# 13-Counter74LS90.net
KiCad netlist of a schematic drawn in Altium Designer
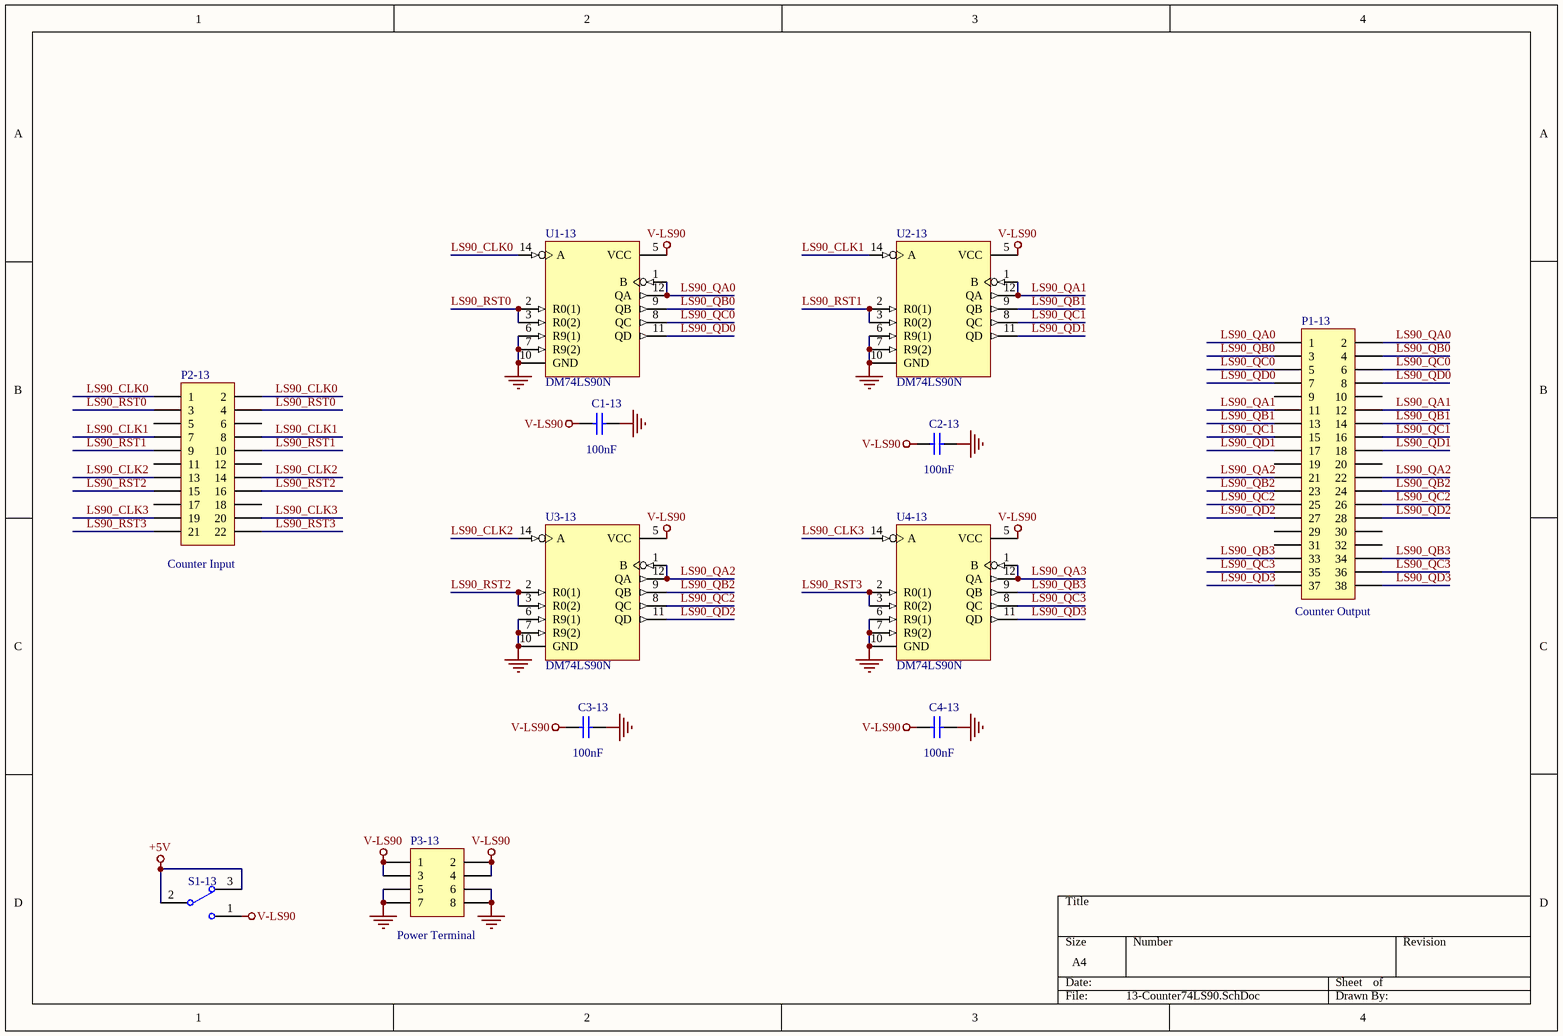
[diagram p0: 13-Counter74LS90.SchDoc]

(export (version "E")
  (design (tool "Eeschema 10.0.6"))
  (components
    (comp (ref "C1-13")
      (value "100nF")
      (footprint "c-0805")
      (description "Capacitor")
      (fields (field (name "Comment") "104") (field (name "PUBLISHER") "Altium Limited"))
      (libsource (lib "Miscellaneous Devices") (part "Cap"))
    )
    (comp (ref "C2-13")
      (value "100nF")
      (footprint "c-0805")
      (description "Capacitor")
      (fields (field (name "Comment") "104") (field (name "PUBLISHER") "Altium Limited"))
      (libsource (lib "Miscellaneous Devices") (part "Cap"))
    )
    (comp (ref "C3-13")
      (value "100nF")
      (footprint "c-0805")
      (description "Capacitor")
      (fields (field (name "Comment") "104") (field (name "PUBLISHER") "Altium Limited"))
      (libsource (lib "Miscellaneous Devices") (part "Cap"))
    )
    (comp (ref "C4-13")
      (value "100nF")
      (footprint "c-0805")
      (description "Capacitor")
      (fields (field (name "Comment") "104") (field (name "PUBLISHER") "Altium Limited"))
      (libsource (lib "Miscellaneous Devices") (part "Cap"))
    )
    (comp (ref "P1-13")
      (value "Counter Output")
      (footprint "JP2.54-F-2x19A")
      (description "Header, 19-Pin, Dual row")
      (fields (field (name "Comment") "Header 19X2"))
      (libsource (lib "Miscellaneous Connectors") (part "Header 19X2"))
    )
    (comp (ref "P2-13")
      (value "Counter Input")
      (footprint "JP2.54-F-2x11A")
      (description "Header, 11-Pin, Dual row")
      (fields (field (name "Comment") "Header 11X2"))
      (libsource (lib "Miscellaneous Connectors") (part "Header 11X2"))
    )
    (comp (ref "P3-13")
      (value "Header 4X2")
      (footprint "JP2.54-F-2x04A")
      (description "Header, 4-Pin, Dual row")
      (fields (field (name "PUBLISHER") "Power Terminal"))
      (libsource (lib "Miscellaneous Connectors") (part "Header 4X2"))
    )
    (comp (ref "S1-13")
      (value "SW-SPDT")
      (footprint "SW-SLIDE-2P-2W")
      (description "SPDT Subminiature Toggle Switch, Right Angle Mounting, Vertical Actuation")
      (fields (field (name "PUBLISHER") "Altium Limited"))
      (libsource (lib "Miscellaneous Devices") (part "SW-SPDT"))
    )
    (comp (ref "U1-13")
      (value "DM74LS90N")
      (footprint "SK-DIP14-300")
      (description "Decade and Binary Counter")
      (fields (field (name "PUBLISHER") "Altium Limited"))
      (libsource (lib "FSC Logic Counter") (part "DM74LS90N"))
    )
    (comp (ref "U2-13")
      (value "DM74LS90N")
      (footprint "SK-DIP14-300")
      (description "Decade and Binary Counter")
      (fields (field (name "PUBLISHER") "Altium Limited"))
      (libsource (lib "FSC Logic Counter") (part "DM74LS90N"))
    )
    (comp (ref "U3-13")
      (value "DM74LS90N")
      (footprint "SK-DIP14-300")
      (description "Decade and Binary Counter")
      (fields (field (name "PUBLISHER") "Altium Limited"))
      (libsource (lib "FSC Logic Counter") (part "DM74LS90N"))
    )
    (comp (ref "U4-13")
      (value "DM74LS90N")
      (footprint "SK-DIP14-300")
      (description "Decade and Binary Counter")
      (fields (field (name "PUBLISHER") "Altium Limited"))
      (libsource (lib "FSC Logic Counter") (part "DM74LS90N"))
    )
  )
  (nets
    (net (code "1") (name "+5V") (class "Default")
      (node (ref "S1-13") (pin "2") (pinfunction "2_2") (pintype "passive"))
      (node (ref "S1-13") (pin "3") (pinfunction "3_3") (pintype "passive"))
    )
    (net (code "2") (name "/LS90_CLK0") (class "Default")
      (node (ref "P2-13") (pin "1") (pinfunction "1_1") (pintype "passive"))
      (node (ref "P2-13") (pin "2") (pinfunction "2_2") (pintype "passive"))
      (node (ref "U1-13") (pin "14") (pinfunction "A_14") (pintype "input"))
    )
    (net (code "3") (name "/LS90_CLK1") (class "Default")
      (node (ref "P2-13") (pin "7") (pinfunction "7_7") (pintype "passive"))
      (node (ref "P2-13") (pin "8") (pinfunction "8_8") (pintype "passive"))
      (node (ref "U2-13") (pin "14") (pinfunction "A_14") (pintype "input"))
    )
    (net (code "4") (name "/LS90_CLK2") (class "Default")
      (node (ref "P2-13") (pin "13") (pinfunction "13_13") (pintype "passive"))
      (node (ref "P2-13") (pin "14") (pinfunction "14_14") (pintype "passive"))
      (node (ref "U3-13") (pin "14") (pinfunction "A_14") (pintype "input"))
    )
    (net (code "5") (name "/LS90_CLK3") (class "Default")
      (node (ref "P2-13") (pin "19") (pinfunction "19_19") (pintype "passive"))
      (node (ref "P2-13") (pin "20") (pinfunction "20_20") (pintype "passive"))
      (node (ref "U4-13") (pin "14") (pinfunction "A_14") (pintype "input"))
    )
    (net (code "6") (name "/LS90_QA0") (class "Default")
      (node (ref "P1-13") (pin "1") (pinfunction "1_1") (pintype "passive"))
      (node (ref "P1-13") (pin "2") (pinfunction "2_2") (pintype "passive"))
      (node (ref "U1-13") (pin "1") (pinfunction "B_1") (pintype "input"))
      (node (ref "U1-13") (pin "12") (pinfunction "QA_12") (pintype "output"))
    )
    (net (code "7") (name "/LS90_QA1") (class "Default")
      (node (ref "P1-13") (pin "11") (pinfunction "11_11") (pintype "passive"))
      (node (ref "P1-13") (pin "12") (pinfunction "12_12") (pintype "passive"))
      (node (ref "U2-13") (pin "1") (pinfunction "B_1") (pintype "input"))
      (node (ref "U2-13") (pin "12") (pinfunction "QA_12") (pintype "output"))
    )
    (net (code "8") (name "/LS90_QA2") (class "Default")
      (node (ref "P1-13") (pin "21") (pinfunction "21_21") (pintype "passive"))
      (node (ref "P1-13") (pin "22") (pinfunction "22_22") (pintype "passive"))
      (node (ref "U3-13") (pin "1") (pinfunction "B_1") (pintype "input"))
      (node (ref "U3-13") (pin "12") (pinfunction "QA_12") (pintype "output"))
    )
    (net (code "9") (name "/LS90_QA3") (class "Default")
      (node (ref "U4-13") (pin "1") (pinfunction "B_1") (pintype "input"))
      (node (ref "U4-13") (pin "12") (pinfunction "QA_12") (pintype "output"))
    )
    (net (code "10") (name "/LS90_QB0") (class "Default")
      (node (ref "P1-13") (pin "3") (pinfunction "3_3") (pintype "passive"))
      (node (ref "P1-13") (pin "4") (pinfunction "4_4") (pintype "passive"))
      (node (ref "U1-13") (pin "9") (pinfunction "QB_9") (pintype "output"))
    )
    (net (code "11") (name "/LS90_QB1") (class "Default")
      (node (ref "P1-13") (pin "13") (pinfunction "13_13") (pintype "passive"))
      (node (ref "P1-13") (pin "14") (pinfunction "14_14") (pintype "passive"))
      (node (ref "U2-13") (pin "9") (pinfunction "QB_9") (pintype "output"))
    )
    (net (code "12") (name "/LS90_QB2") (class "Default")
      (node (ref "P1-13") (pin "23") (pinfunction "23_23") (pintype "passive"))
      (node (ref "P1-13") (pin "24") (pinfunction "24_24") (pintype "passive"))
      (node (ref "U3-13") (pin "9") (pinfunction "QB_9") (pintype "output"))
    )
    (net (code "13") (name "/LS90_QB3") (class "Default")
      (node (ref "P1-13") (pin "33") (pinfunction "33_33") (pintype "passive"))
      (node (ref "P1-13") (pin "34") (pinfunction "34_34") (pintype "passive"))
      (node (ref "U4-13") (pin "9") (pinfunction "QB_9") (pintype "output"))
    )
    (net (code "14") (name "/LS90_QC0") (class "Default")
      (node (ref "P1-13") (pin "5") (pinfunction "5_5") (pintype "passive"))
      (node (ref "P1-13") (pin "6") (pinfunction "6_6") (pintype "passive"))
      (node (ref "U1-13") (pin "8") (pinfunction "QC_8") (pintype "output"))
    )
    (net (code "15") (name "/LS90_QC1") (class "Default")
      (node (ref "P1-13") (pin "15") (pinfunction "15_15") (pintype "passive"))
      (node (ref "P1-13") (pin "16") (pinfunction "16_16") (pintype "passive"))
      (node (ref "U2-13") (pin "8") (pinfunction "QC_8") (pintype "output"))
    )
    (net (code "16") (name "/LS90_QC2") (class "Default")
      (node (ref "P1-13") (pin "25") (pinfunction "25_25") (pintype "passive"))
      (node (ref "P1-13") (pin "26") (pinfunction "26_26") (pintype "passive"))
      (node (ref "U3-13") (pin "8") (pinfunction "QC_8") (pintype "output"))
    )
    (net (code "17") (name "/LS90_QC3") (class "Default")
      (node (ref "P1-13") (pin "35") (pinfunction "35_35") (pintype "passive"))
      (node (ref "P1-13") (pin "36") (pinfunction "36_36") (pintype "passive"))
      (node (ref "U4-13") (pin "8") (pinfunction "QC_8") (pintype "output"))
    )
    (net (code "18") (name "/LS90_QD0") (class "Default")
      (node (ref "P1-13") (pin "7") (pinfunction "7_7") (pintype "passive"))
      (node (ref "P1-13") (pin "8") (pinfunction "8_8") (pintype "passive"))
      (node (ref "U1-13") (pin "11") (pinfunction "QD_11") (pintype "output"))
    )
    (net (code "19") (name "/LS90_QD1") (class "Default")
      (node (ref "P1-13") (pin "17") (pinfunction "17_17") (pintype "passive"))
      (node (ref "P1-13") (pin "18") (pinfunction "18_18") (pintype "passive"))
      (node (ref "U2-13") (pin "11") (pinfunction "QD_11") (pintype "output"))
    )
    (net (code "20") (name "/LS90_QD2") (class "Default")
      (node (ref "P1-13") (pin "27") (pinfunction "27_27") (pintype "passive"))
      (node (ref "P1-13") (pin "28") (pinfunction "28_28") (pintype "passive"))
      (node (ref "U3-13") (pin "11") (pinfunction "QD_11") (pintype "output"))
    )
    (net (code "21") (name "/LS90_QD3") (class "Default")
      (node (ref "P1-13") (pin "37") (pinfunction "37_37") (pintype "passive"))
      (node (ref "P1-13") (pin "38") (pinfunction "38_38") (pintype "passive"))
      (node (ref "U4-13") (pin "11") (pinfunction "QD_11") (pintype "output"))
    )
    (net (code "22") (name "/LS90_RST0") (class "Default")
      (node (ref "P2-13") (pin "3") (pinfunction "3_3") (pintype "passive"))
      (node (ref "P2-13") (pin "4") (pinfunction "4_4") (pintype "passive"))
      (node (ref "U1-13") (pin "2") (pinfunction "R0(1)_2") (pintype "input"))
      (node (ref "U1-13") (pin "3") (pinfunction "R0(2)_3") (pintype "input"))
    )
    (net (code "23") (name "/LS90_RST1") (class "Default")
      (node (ref "P2-13") (pin "10") (pinfunction "10_10") (pintype "passive"))
      (node (ref "P2-13") (pin "9") (pinfunction "9_9") (pintype "passive"))
      (node (ref "U2-13") (pin "2") (pinfunction "R0(1)_2") (pintype "input"))
      (node (ref "U2-13") (pin "3") (pinfunction "R0(2)_3") (pintype "input"))
    )
    (net (code "24") (name "/LS90_RST2") (class "Default")
      (node (ref "P2-13") (pin "15") (pinfunction "15_15") (pintype "passive"))
      (node (ref "P2-13") (pin "16") (pinfunction "16_16") (pintype "passive"))
      (node (ref "U3-13") (pin "2") (pinfunction "R0(1)_2") (pintype "input"))
      (node (ref "U3-13") (pin "3") (pinfunction "R0(2)_3") (pintype "input"))
    )
    (net (code "25") (name "/LS90_RST3") (class "Default")
      (node (ref "P2-13") (pin "21") (pinfunction "21_21") (pintype "passive"))
      (node (ref "P2-13") (pin "22") (pinfunction "22_22") (pintype "passive"))
      (node (ref "U4-13") (pin "2") (pinfunction "R0(1)_2") (pintype "input"))
      (node (ref "U4-13") (pin "3") (pinfunction "R0(2)_3") (pintype "input"))
    )
    (net (code "26") (name "GND") (class "Default")
      (node (ref "C1-13") (pin "2") (pinfunction "2_2") (pintype "passive"))
      (node (ref "C2-13") (pin "2") (pinfunction "2_2") (pintype "passive"))
      (node (ref "C3-13") (pin "2") (pinfunction "2_2") (pintype "passive"))
      (node (ref "C4-13") (pin "2") (pinfunction "2_2") (pintype "passive"))
      (node (ref "P3-13") (pin "5") (pinfunction "5_5") (pintype "passive"))
      (node (ref "P3-13") (pin "6") (pinfunction "6_6") (pintype "passive"))
      (node (ref "P3-13") (pin "7") (pinfunction "7_7") (pintype "passive"))
      (node (ref "P3-13") (pin "8") (pinfunction "8_8") (pintype "passive"))
      (node (ref "U1-13") (pin "10") (pinfunction "GND_10") (pintype "power_in"))
      (node (ref "U1-13") (pin "6") (pinfunction "R9(1)_6") (pintype "input"))
      (node (ref "U1-13") (pin "7") (pinfunction "R9(2)_7") (pintype "input"))
      (node (ref "U2-13") (pin "10") (pinfunction "GND_10") (pintype "power_in"))
      (node (ref "U2-13") (pin "6") (pinfunction "R9(1)_6") (pintype "input"))
      (node (ref "U2-13") (pin "7") (pinfunction "R9(2)_7") (pintype "input"))
      (node (ref "U3-13") (pin "10") (pinfunction "GND_10") (pintype "power_in"))
      (node (ref "U3-13") (pin "6") (pinfunction "R9(1)_6") (pintype "input"))
      (node (ref "U3-13") (pin "7") (pinfunction "R9(2)_7") (pintype "input"))
      (node (ref "U4-13") (pin "10") (pinfunction "GND_10") (pintype "power_in"))
      (node (ref "U4-13") (pin "6") (pinfunction "R9(1)_6") (pintype "input"))
      (node (ref "U4-13") (pin "7") (pinfunction "R9(2)_7") (pintype "input"))
    )
    (net (code "27") (name "V-LS90") (class "Default")
      (node (ref "C1-13") (pin "1") (pinfunction "1_1") (pintype "passive"))
      (node (ref "C2-13") (pin "1") (pinfunction "1_1") (pintype "passive"))
      (node (ref "C3-13") (pin "1") (pinfunction "1_1") (pintype "passive"))
      (node (ref "C4-13") (pin "1") (pinfunction "1_1") (pintype "passive"))
      (node (ref "P3-13") (pin "1") (pinfunction "1_1") (pintype "passive"))
      (node (ref "P3-13") (pin "2") (pinfunction "2_2") (pintype "passive"))
      (node (ref "P3-13") (pin "3") (pinfunction "3_3") (pintype "passive"))
      (node (ref "P3-13") (pin "4") (pinfunction "4_4") (pintype "passive"))
      (node (ref "S1-13") (pin "1") (pinfunction "1_1") (pintype "passive"))
      (node (ref "U1-13") (pin "5") (pinfunction "VCC_5") (pintype "power_in"))
      (node (ref "U2-13") (pin "5") (pinfunction "VCC_5") (pintype "power_in"))
      (node (ref "U3-13") (pin "5") (pinfunction "VCC_5") (pintype "power_in"))
      (node (ref "U4-13") (pin "5") (pinfunction "VCC_5") (pintype "power_in"))
    )
    (net (code "28") (name "unconnected-(P1-13-Pad9)") (class "Default")
      (node (ref "P1-13") (pin "9") (pinfunction "9_9") (pintype "passive"))
    )
    (net (code "29") (name "unconnected-(P1-13-Pad10)") (class "Default")
      (node (ref "P1-13") (pin "10") (pinfunction "10_10") (pintype "passive"))
    )
    (net (code "30") (name "unconnected-(P1-13-Pad19)") (class "Default")
      (node (ref "P1-13") (pin "19") (pinfunction "19_19") (pintype "passive"))
    )
    (net (code "31") (name "unconnected-(P1-13-Pad20)") (class "Default")
      (node (ref "P1-13") (pin "20") (pinfunction "20_20") (pintype "passive"))
    )
    (net (code "32") (name "unconnected-(P1-13-Pad29)") (class "Default")
      (node (ref "P1-13") (pin "29") (pinfunction "29_29") (pintype "passive"))
    )
    (net (code "33") (name "unconnected-(P1-13-Pad30)") (class "Default")
      (node (ref "P1-13") (pin "30") (pinfunction "30_30") (pintype "passive"))
    )
    (net (code "34") (name "unconnected-(P1-13-Pad31)") (class "Default")
      (node (ref "P1-13") (pin "31") (pinfunction "31_31") (pintype "passive"))
    )
    (net (code "35") (name "unconnected-(P1-13-Pad32)") (class "Default")
      (node (ref "P1-13") (pin "32") (pinfunction "32_32") (pintype "passive"))
    )
    (net (code "36") (name "unconnected-(P2-13-Pad5)") (class "Default")
      (node (ref "P2-13") (pin "5") (pinfunction "5_5") (pintype "passive"))
    )
    (net (code "37") (name "unconnected-(P2-13-Pad6)") (class "Default")
      (node (ref "P2-13") (pin "6") (pinfunction "6_6") (pintype "passive"))
    )
    (net (code "38") (name "unconnected-(P2-13-Pad11)") (class "Default")
      (node (ref "P2-13") (pin "11") (pinfunction "11_11") (pintype "passive"))
    )
    (net (code "39") (name "unconnected-(P2-13-Pad12)") (class "Default")
      (node (ref "P2-13") (pin "12") (pinfunction "12_12") (pintype "passive"))
    )
    (net (code "40") (name "unconnected-(P2-13-Pad17)") (class "Default")
      (node (ref "P2-13") (pin "17") (pinfunction "17_17") (pintype "passive"))
    )
    (net (code "41") (name "unconnected-(P2-13-Pad18)") (class "Default")
      (node (ref "P2-13") (pin "18") (pinfunction "18_18") (pintype "passive"))
    )
  )
)
